# LED_DRIVER.net
KiCad netlist of a schematic drawn in Altium Designer
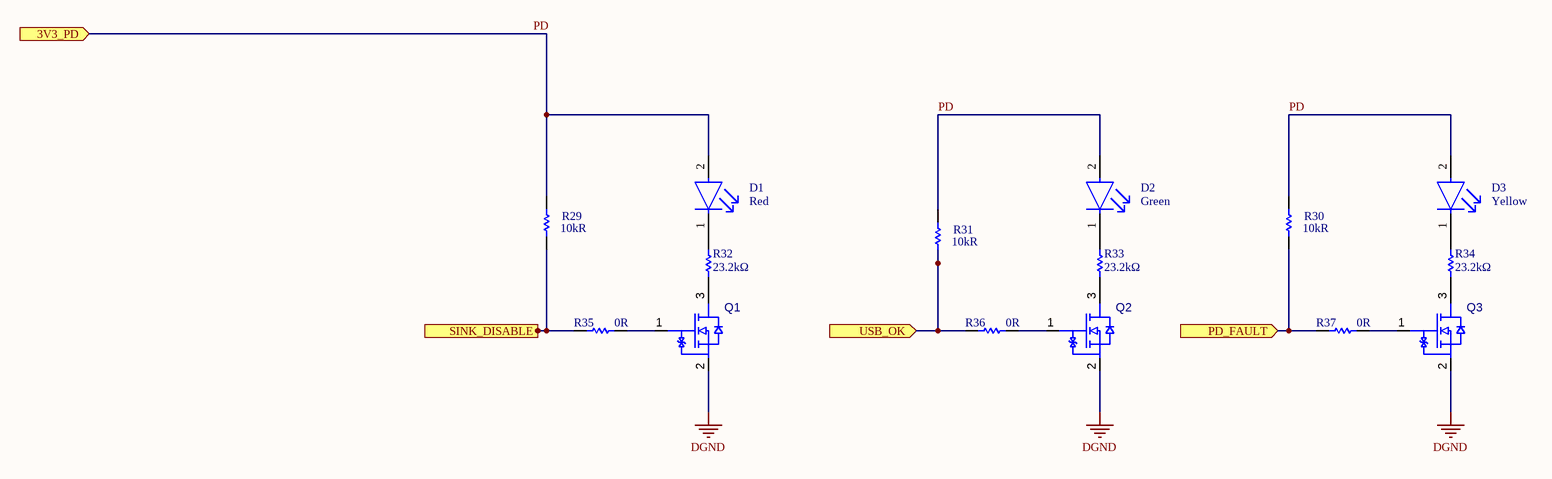
[diagram p0: LED_DRIVER.SchDoc]

(export (version "E")
  (design (tool "Eeschema 10.0.6"))
  (components
    (comp (ref "D1")
      (value "Red")
      (footprint "FP-VLMO1500-GS08-MFG")
      (description "RED 0402 VLMx1500")
      (fields (field (name "Comment") "VLMS1500-GS08"))
      (libsource (lib "Altium Content Vault") (part "75a0115997dd6a71327e26aab64f6f8"))
    )
    (comp (ref "D2")
      (value "Green")
      (footprint "FP-VLMO1500-GS08-MFG")
      (description "GREEN 0402 VLMx1500")
      (fields (field (name "Comment") "VLMG1500-GS08"))
      (libsource (lib "Altium Content Vault") (part "75a0115997dd6a71327e26aab64f6f8"))
    )
    (comp (ref "D3")
      (value "Yellow")
      (footprint "FP-VLMO1500-GS08-MFG")
      (description "YELLOW 0402 VLMx1500")
      (fields (field (name "Comment") "VLMY1500-GS08"))
      (libsource (lib "Altium Content Vault") (part "75a0115997dd6a71327e26aab64f6f8"))
    )
    (comp (ref "Q1")
      (value "RUM002N05T2L")
      (footprint "ROHM-SOT723-3_V")
      (description "Nch Small Signal MOSFET, 50 V, 200 mA, 3-Pin SOT723, RoHS, Tape and Reel")
      (libsource (lib "Digital Shovel") (part "CMP-00005-6"))
    )
    (comp (ref "Q2")
      (value "RUM002N05T2L")
      (footprint "ROHM-SOT723-3_V")
      (description "Nch Small Signal MOSFET, 50 V, 200 mA, 3-Pin SOT723, RoHS, Tape and Reel")
      (libsource (lib "Digital Shovel") (part "CMP-00005-6"))
    )
    (comp (ref "Q3")
      (value "RUM002N05T2L")
      (footprint "ROHM-SOT723-3_V")
      (description "Nch Small Signal MOSFET, 50 V, 200 mA, 3-Pin SOT723, RoHS, Tape and Reel")
      (libsource (lib "Digital Shovel") (part "CMP-00005-6"))
    )
    (comp (ref "R29")
      (value "10kR")
      (footprint "RESC1005X40X25LL10T10")
      (fields (field (name "Comment") "RK73H1ETTP1002F"))
      (libsource (lib "Digital Shovel") (part "RES"))
    )
    (comp (ref "R30")
      (value "10kR")
      (footprint "RESC1005X40X25LL10T10")
      (fields (field (name "Comment") "RK73H1ETTP1002F"))
      (libsource (lib "Digital Shovel") (part "RES"))
    )
    (comp (ref "R31")
      (value "10kR")
      (footprint "RESC1005X40X25LL10T10")
      (fields (field (name "Comment") "RK73H1ETTP1002F"))
      (libsource (lib "Digital Shovel") (part "RES"))
    )
    (comp (ref "R32")
      (value "23.2kΩ")
      (footprint "RESC1005X40X25LL10T10")
      (fields (field (name "Comment") "RK73H1ETTP2322F"))
      (libsource (lib "Digital Shovel") (part "RES"))
    )
    (comp (ref "R33")
      (value "23.2kΩ")
      (footprint "RESC1005X40X25LL10T10")
      (fields (field (name "Comment") "RK73H1ETTP2322F"))
      (libsource (lib "Digital Shovel") (part "RES"))
    )
    (comp (ref "R34")
      (value "23.2kΩ")
      (footprint "RESC1005X40X25LL10T10")
      (fields (field (name "Comment") "RK73H1ETTP2322F"))
      (libsource (lib "Digital Shovel") (part "RES"))
    )
    (comp (ref "R35")
      (value "0R")
      (footprint "FP-RK73Z1E-IPC_B")
      (description "Metal Glaze/thick Film, 0ohm, Surface Mount, 0402")
      (fields (field (name "Comment") "RK73Z1ETTP"))
      (libsource (lib "Digital Shovel") (part "1029c3af85768c4190bb7ad29bc67b5"))
    )
    (comp (ref "R36")
      (value "0R")
      (footprint "FP-RK73Z1E-IPC_B")
      (description "Metal Glaze/thick Film, 0ohm, Surface Mount, 0402")
      (fields (field (name "Comment") "RK73Z1ETTP"))
      (libsource (lib "Digital Shovel") (part "1029c3af85768c4190bb7ad29bc67b5"))
    )
    (comp (ref "R37")
      (value "0R")
      (footprint "FP-RK73Z1E-IPC_B")
      (description "Metal Glaze/thick Film, 0ohm, Surface Mount, 0402")
      (fields (field (name "Comment") "RK73Z1ETTP"))
      (libsource (lib "Digital Shovel") (part "1029c3af85768c4190bb7ad29bc67b5"))
    )
  )
  (nets
    (net (code "1") (name "/PD") (class "Default")
      (node (ref "D1") (pin "2") (pinfunction "A_2") (pintype "passive"))
      (node (ref "D2") (pin "2") (pinfunction "A_2") (pintype "passive"))
      (node (ref "D3") (pin "2") (pinfunction "A_2") (pintype "passive"))
      (node (ref "R29") (pin "1") (pinfunction "1_1") (pintype "passive"))
      (node (ref "R30") (pin "1") (pinfunction "1_1") (pintype "passive"))
      (node (ref "R31") (pin "1") (pinfunction "1_1") (pintype "passive"))
    )
    (net (code "2") (name "/PD_FAULT") (class "Default")
      (node (ref "R30") (pin "2") (pinfunction "2_2") (pintype "passive"))
      (node (ref "R37") (pin "1") (pinfunction "1_1") (pintype "passive"))
    )
    (net (code "3") (name "/SINK_DISABLE") (class "Default")
      (node (ref "R29") (pin "2") (pinfunction "2_2") (pintype "passive"))
      (node (ref "R35") (pin "1") (pinfunction "1_1") (pintype "passive"))
    )
    (net (code "4") (name "/USB_OK") (class "Default")
      (node (ref "R31") (pin "2") (pinfunction "2_2") (pintype "passive"))
      (node (ref "R36") (pin "1") (pinfunction "1_1") (pintype "passive"))
    )
    (net (code "5") (name "DGND") (class "Default")
      (node (ref "Q1") (pin "2") (pinfunction "S_2") (pintype "passive"))
      (node (ref "Q2") (pin "2") (pinfunction "S_2") (pintype "passive"))
      (node (ref "Q3") (pin "2") (pinfunction "S_2") (pintype "passive"))
    )
    (net (code "6") (name "Net-(D1-C)") (class "Default")
      (node (ref "D1") (pin "1") (pinfunction "C_1") (pintype "passive"))
      (node (ref "R32") (pin "2") (pinfunction "2_2") (pintype "passive"))
    )
    (net (code "7") (name "Net-(D2-C)") (class "Default")
      (node (ref "D2") (pin "1") (pinfunction "C_1") (pintype "passive"))
      (node (ref "R33") (pin "2") (pinfunction "2_2") (pintype "passive"))
    )
    (net (code "8") (name "Net-(D3-C)") (class "Default")
      (node (ref "D3") (pin "1") (pinfunction "C_1") (pintype "passive"))
      (node (ref "R34") (pin "2") (pinfunction "2_2") (pintype "passive"))
    )
    (net (code "9") (name "Net-(Q1-D)") (class "Default")
      (node (ref "Q1") (pin "3") (pinfunction "D_3") (pintype "passive"))
      (node (ref "R32") (pin "1") (pinfunction "1_1") (pintype "passive"))
    )
    (net (code "10") (name "Net-(Q1-G)") (class "Default")
      (node (ref "Q1") (pin "1") (pinfunction "G_1") (pintype "passive"))
      (node (ref "R35") (pin "2") (pinfunction "2_2") (pintype "passive"))
    )
    (net (code "11") (name "Net-(Q2-D)") (class "Default")
      (node (ref "Q2") (pin "3") (pinfunction "D_3") (pintype "passive"))
      (node (ref "R33") (pin "1") (pinfunction "1_1") (pintype "passive"))
    )
    (net (code "12") (name "Net-(Q2-G)") (class "Default")
      (node (ref "Q2") (pin "1") (pinfunction "G_1") (pintype "passive"))
      (node (ref "R36") (pin "2") (pinfunction "2_2") (pintype "passive"))
    )
    (net (code "13") (name "Net-(Q3-D)") (class "Default")
      (node (ref "Q3") (pin "3") (pinfunction "D_3") (pintype "passive"))
      (node (ref "R34") (pin "1") (pinfunction "1_1") (pintype "passive"))
    )
    (net (code "14") (name "Net-(Q3-G)") (class "Default")
      (node (ref "Q3") (pin "1") (pinfunction "G_1") (pintype "passive"))
      (node (ref "R37") (pin "2") (pinfunction "2_2") (pintype "passive"))
    )
  )
)
